# led.net
KiCad netlist of a schematic drawn in Altium Designer
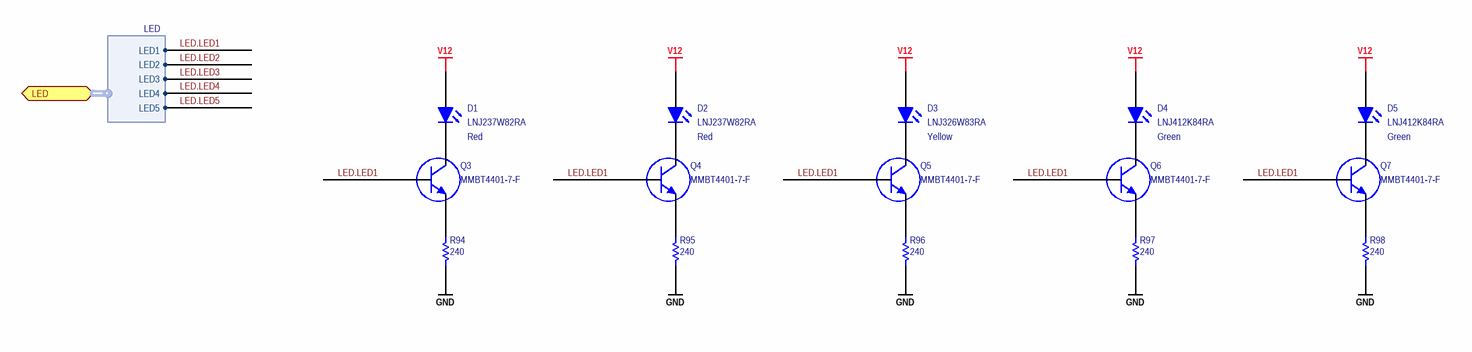
[diagram p0: led.SchDoc]

(export (version "E")
  (design (tool "Eeschema 10.0.6"))
  (components
    (comp (ref "D1")
      (value "LNJ237W82RA")
      (footprint "0603_LED")
      (description "LED, SMT 0603, Color Red, 5mA, 1.85V")
      (fields (field (name "MANUFACTURER") "Panasonic"))
      (libsource (lib "generic") (part "LED0603RD"))
    )
    (comp (ref "D2")
      (value "LNJ237W82RA")
      (footprint "0603_LED")
      (description "LED, SMT 0603, Color Red, 5mA, 1.85V")
      (fields (field (name "MANUFACTURER") "Panasonic"))
      (libsource (lib "generic") (part "LED0603RD"))
    )
    (comp (ref "D3")
      (value "LNJ326W83RA")
      (footprint "0603_LED")
      (description "LED, SMT 0603, Color Green, 10mA, 2.05V")
      (fields (field (name "MANUFACTURER") "Panasonic"))
      (libsource (lib "generic") (part "LED0603GR"))
    )
    (comp (ref "D4")
      (value "LNJ412K84RA")
      (footprint "0603_LED")
      (description "LED, SMT 0603, Color Yellow, 10mA, 2.05V")
      (fields (field (name "MANUFACTURER") "Panasonic"))
      (libsource (lib "generic") (part "LED0603Y"))
    )
    (comp (ref "D5")
      (value "LNJ412K84RA")
      (footprint "0603_LED")
      (description "LED, SMT 0603, Color Yellow, 10mA, 2.05V")
      (fields (field (name "MANUFACTURER") "Panasonic"))
      (libsource (lib "generic") (part "LED0603Y"))
    )
    (comp (ref "Q3")
      (value "NPN Transistor")
      (footprint "generic:SOT23")
      (description "NPN Small Signal Transistor SMD SOT-23")
      (fields (field (name "MANUFACTURER P/N") "MMBT4401-7-F") (field (name "MANUFACTURER") "Diodes, Inc."))
      (libsource (lib "diodes_inc") (part "MMBT4401-7-F"))
    )
    (comp (ref "Q4")
      (value "NPN Transistor")
      (footprint "generic:SOT23")
      (description "NPN Small Signal Transistor SMD SOT-23")
      (fields (field (name "MANUFACTURER P/N") "MMBT4401-7-F") (field (name "MANUFACTURER") "Diodes, Inc."))
      (libsource (lib "diodes_inc") (part "MMBT4401-7-F"))
    )
    (comp (ref "Q5")
      (value "NPN Transistor")
      (footprint "generic:SOT23")
      (description "NPN Small Signal Transistor SMD SOT-23")
      (fields (field (name "MANUFACTURER P/N") "MMBT4401-7-F") (field (name "MANUFACTURER") "Diodes, Inc."))
      (libsource (lib "diodes_inc") (part "MMBT4401-7-F"))
    )
    (comp (ref "Q6")
      (value "NPN Transistor")
      (footprint "generic:SOT23")
      (description "NPN Small Signal Transistor SMD SOT-23")
      (fields (field (name "MANUFACTURER P/N") "MMBT4401-7-F") (field (name "MANUFACTURER") "Diodes, Inc."))
      (libsource (lib "diodes_inc") (part "MMBT4401-7-F"))
    )
    (comp (ref "Q7")
      (value "NPN Transistor")
      (footprint "generic:SOT23")
      (description "NPN Small Signal Transistor SMD SOT-23")
      (fields (field (name "MANUFACTURER P/N") "MMBT4401-7-F") (field (name "MANUFACTURER") "Diodes, Inc."))
      (libsource (lib "diodes_inc") (part "MMBT4401-7-F"))
    )
    (comp (ref "R94")
      (value "240")
      (footprint "RESC1608X55N")
      (description "Thick Film Resistor 240 Ohms +/-1% 0.1W 75V SMD 0603")
      (fields (field (name "TOLERANCE") "+/-1%") (field (name "MANUFACTURER") "Panasonic - ECG"))
      (libsource (lib "brinton") (part "RES"))
    )
    (comp (ref "R95")
      (value "240")
      (footprint "RESC1608X55N")
      (description "Thick Film Resistor 240 Ohms +/-1% 0.1W 75V SMD 0603")
      (fields (field (name "TOLERANCE") "+/-1%") (field (name "MANUFACTURER") "Panasonic - ECG"))
      (libsource (lib "brinton") (part "RES"))
    )
    (comp (ref "R96")
      (value "240")
      (footprint "RESC1608X55N")
      (description "Thick Film Resistor 240 Ohms +/-1% 0.1W 75V SMD 0603")
      (fields (field (name "TOLERANCE") "+/-1%") (field (name "MANUFACTURER") "Panasonic - ECG"))
      (libsource (lib "brinton") (part "RES"))
    )
    (comp (ref "R97")
      (value "240")
      (footprint "RESC1608X55N")
      (description "Thick Film Resistor 240 Ohms +/-1% 0.1W 75V SMD 0603")
      (fields (field (name "TOLERANCE") "+/-1%") (field (name "MANUFACTURER") "Panasonic - ECG"))
      (libsource (lib "brinton") (part "RES"))
    )
    (comp (ref "R98")
      (value "240")
      (footprint "RESC1608X55N")
      (description "Thick Film Resistor 240 Ohms +/-1% 0.1W 75V SMD 0603")
      (fields (field (name "TOLERANCE") "+/-1%") (field (name "MANUFACTURER") "Panasonic - ECG"))
      (libsource (lib "brinton") (part "RES"))
    )
  )
  (nets
    (net (code "2") (name "/LED.LED1") (class "Default")
      (node (ref "Q3") (pin "1") (pinfunction "B_1") (pintype "passive"))
      (node (ref "Q4") (pin "1") (pinfunction "B_1") (pintype "passive"))
      (node (ref "Q5") (pin "1") (pinfunction "B_1") (pintype "passive"))
      (node (ref "Q6") (pin "1") (pinfunction "B_1") (pintype "passive"))
      (node (ref "Q7") (pin "1") (pinfunction "B_1") (pintype "passive"))
    )
    (net (code "8") (name "GND") (class "Default")
      (node (ref "R94") (pin "2") (pinfunction "2_2") (pintype "passive"))
      (node (ref "R95") (pin "2") (pinfunction "2_2") (pintype "passive"))
      (node (ref "R96") (pin "2") (pinfunction "2_2") (pintype "passive"))
      (node (ref "R97") (pin "2") (pinfunction "2_2") (pintype "passive"))
      (node (ref "R98") (pin "2") (pinfunction "2_2") (pintype "passive"))
    )
    (net (code "9") (name "Net-(D1-K)") (class "Default")
      (node (ref "D1") (pin "2") (pinfunction "K_2") (pintype "passive"))
      (node (ref "Q3") (pin "3") (pinfunction "C_3") (pintype "passive"))
    )
    (net (code "10") (name "Net-(D2-K)") (class "Default")
      (node (ref "D2") (pin "2") (pinfunction "K_2") (pintype "passive"))
      (node (ref "Q4") (pin "3") (pinfunction "C_3") (pintype "passive"))
    )
    (net (code "11") (name "Net-(D3-K)") (class "Default")
      (node (ref "D3") (pin "2") (pinfunction "K_2") (pintype "passive"))
      (node (ref "Q5") (pin "3") (pinfunction "C_3") (pintype "passive"))
    )
    (net (code "12") (name "Net-(D4-K)") (class "Default")
      (node (ref "D4") (pin "2") (pinfunction "K_2") (pintype "passive"))
      (node (ref "Q6") (pin "3") (pinfunction "C_3") (pintype "passive"))
    )
    (net (code "13") (name "Net-(D5-K)") (class "Default")
      (node (ref "D5") (pin "2") (pinfunction "K_2") (pintype "passive"))
      (node (ref "Q7") (pin "3") (pinfunction "C_3") (pintype "passive"))
    )
    (net (code "14") (name "Net-(Q3-E)") (class "Default")
      (node (ref "Q3") (pin "2") (pinfunction "E_2") (pintype "passive"))
      (node (ref "R94") (pin "1") (pinfunction "1_1") (pintype "passive"))
    )
    (net (code "15") (name "Net-(Q4-E)") (class "Default")
      (node (ref "Q4") (pin "2") (pinfunction "E_2") (pintype "passive"))
      (node (ref "R95") (pin "1") (pinfunction "1_1") (pintype "passive"))
    )
    (net (code "16") (name "Net-(Q5-E)") (class "Default")
      (node (ref "Q5") (pin "2") (pinfunction "E_2") (pintype "passive"))
      (node (ref "R96") (pin "1") (pinfunction "1_1") (pintype "passive"))
    )
    (net (code "17") (name "Net-(Q6-E)") (class "Default")
      (node (ref "Q6") (pin "2") (pinfunction "E_2") (pintype "passive"))
      (node (ref "R97") (pin "1") (pinfunction "1_1") (pintype "passive"))
    )
    (net (code "18") (name "Net-(Q7-E)") (class "Default")
      (node (ref "Q7") (pin "2") (pinfunction "E_2") (pintype "passive"))
      (node (ref "R98") (pin "1") (pinfunction "1_1") (pintype "passive"))
    )
    (net (code "19") (name "V12") (class "Default")
      (node (ref "D1") (pin "1") (pinfunction "A_1") (pintype "passive"))
      (node (ref "D2") (pin "1") (pinfunction "A_1") (pintype "passive"))
      (node (ref "D3") (pin "1") (pinfunction "A_1") (pintype "passive"))
      (node (ref "D4") (pin "1") (pinfunction "A_1") (pintype "passive"))
      (node (ref "D5") (pin "1") (pinfunction "A_1") (pintype "passive"))
    )
  )
)
